# schematic.net
KiCad netlist of a schematic drawn in EAGLE
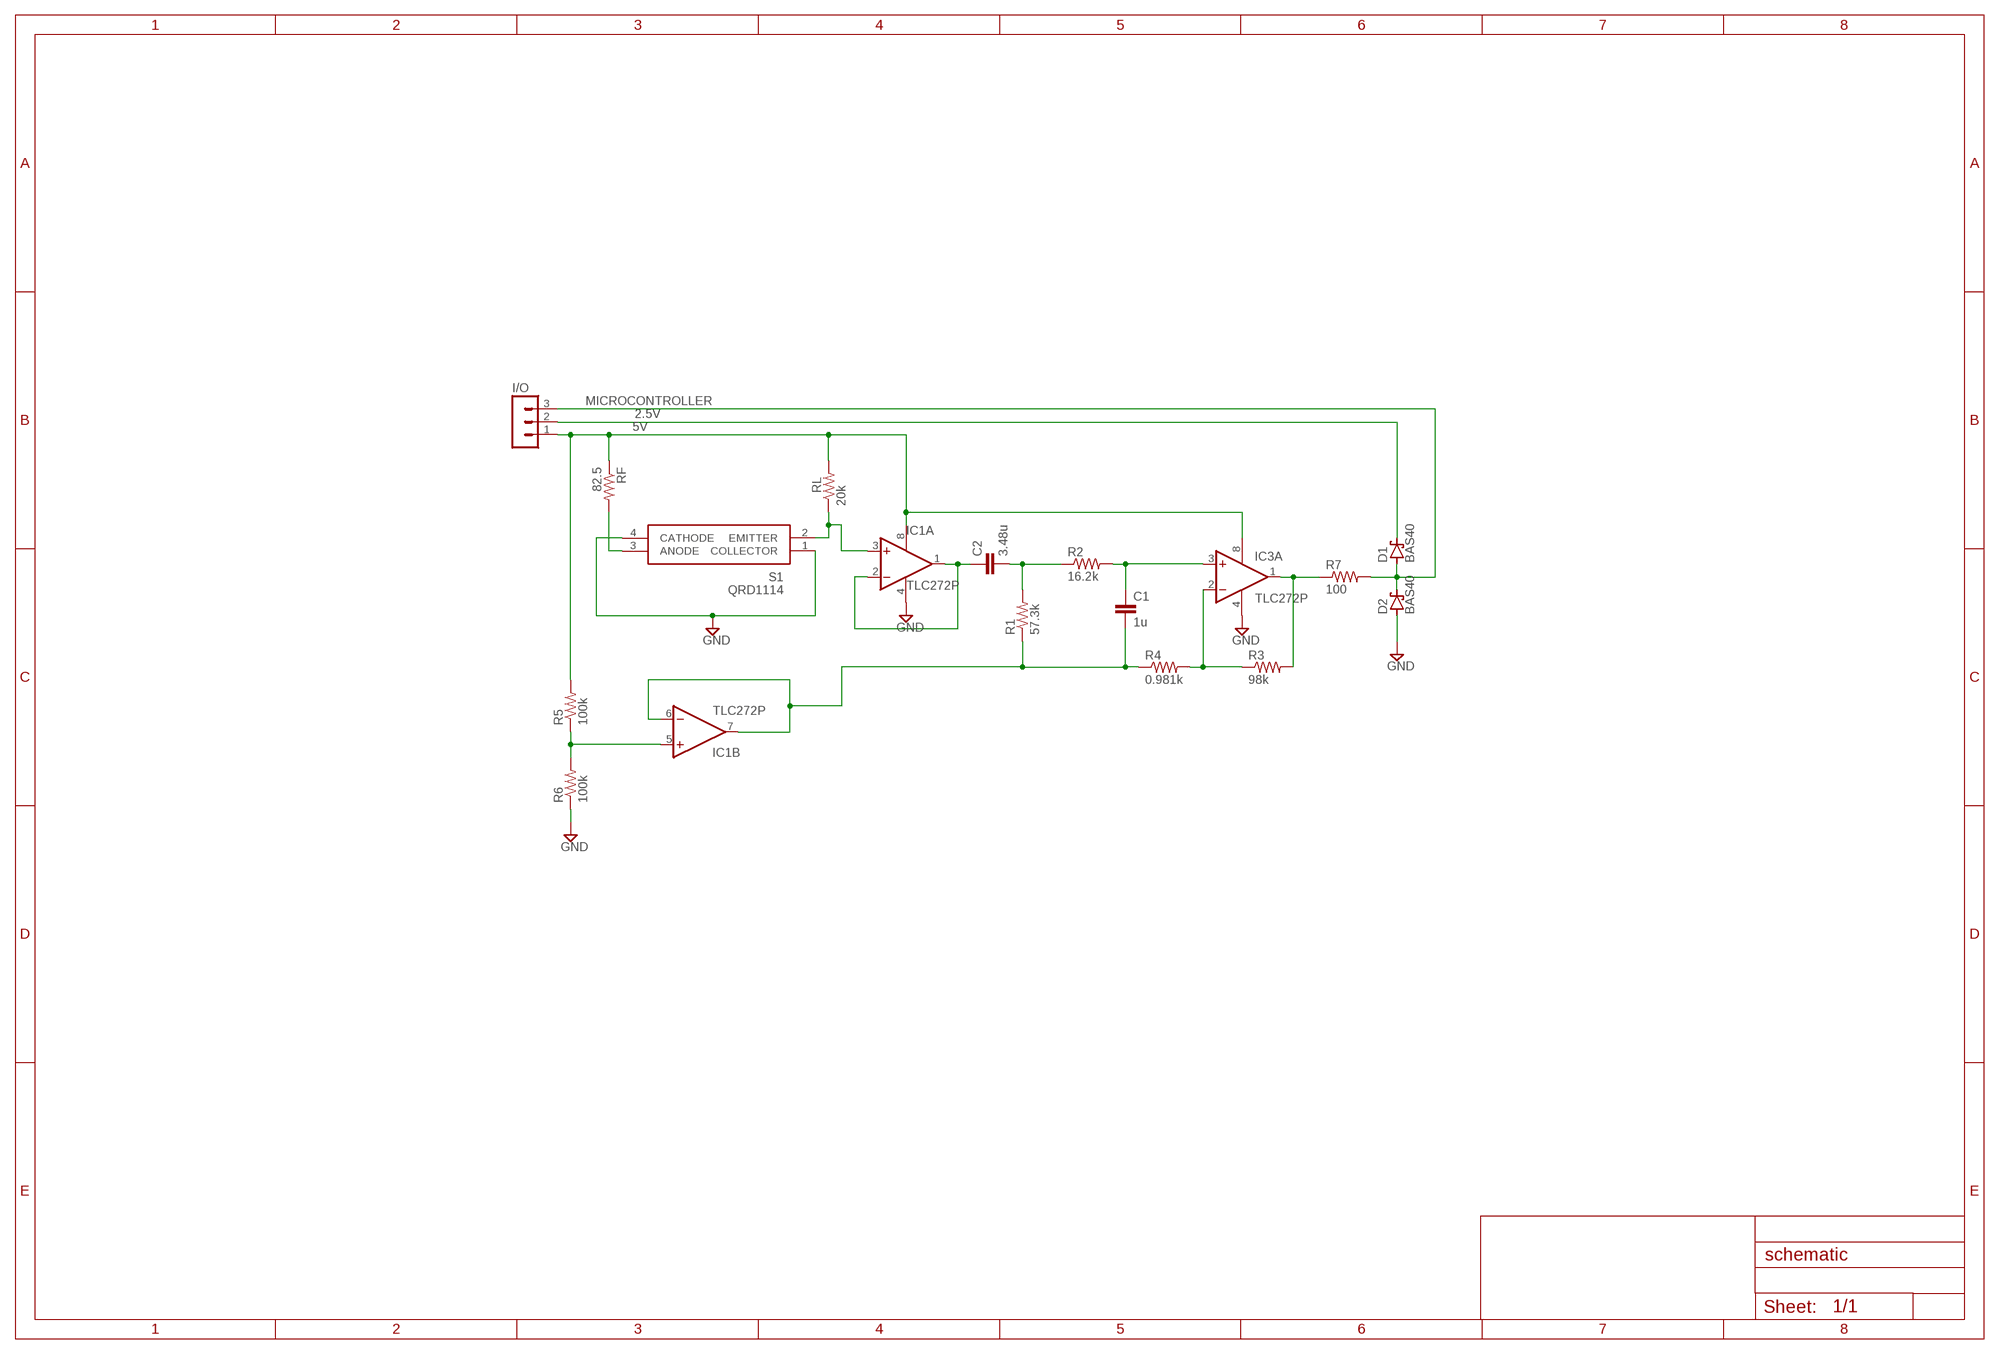
[diagram p0: schematic, sheet 1]

(export (version "E")
  (design (tool "Eeschema 10.0.6"))
  (components
    (comp (ref "C1")
      (value "1u")
      (footprint "eagle-import:C0402")
      (libsource (lib "eagle-import") (part "C-EUC0402"))
    )
    (comp (ref "C2")
      (value "3.48u")
      (footprint "eagle-import:C0402")
      (libsource (lib "eagle-import") (part "C-EUC0402"))
    )
    (comp (ref "D1")
      (value "BAS40")
      (footprint "eagle-import:SOT23")
      (libsource (lib "eagle-import") (part "BAS40"))
    )
    (comp (ref "D2")
      (value "BAS40")
      (footprint "eagle-import:SOT23")
      (libsource (lib "eagle-import") (part "BAS40"))
    )
    (comp (ref "I/O")
      (value "MA03-1")
      (footprint "eagle-import:MA03-1")
      (libsource (lib "eagle-import") (part "MA03-1"))
    )
    (comp (ref "IC1")
      (value "TLC272P")
      (footprint "eagle-import:DIL08")
      (libsource (lib "eagle-import") (part "TLC272P"))
    )
    (comp (ref "IC3")
      (value "TLC272P")
      (footprint "eagle-import:DIL08")
      (libsource (lib "eagle-import") (part "TLC272P"))
    )
    (comp (ref "R1")
      (value "57.3k")
      (footprint "eagle-import:M0805")
      (libsource (lib "eagle-import") (part "R-US_M0805"))
    )
    (comp (ref "R2")
      (value "16.2k")
      (footprint "eagle-import:M0805")
      (libsource (lib "eagle-import") (part "R-US_M0805"))
    )
    (comp (ref "R3")
      (value "98k")
      (footprint "eagle-import:M0805")
      (libsource (lib "eagle-import") (part "R-US_M0805"))
    )
    (comp (ref "R4")
      (value "0.981k")
      (footprint "eagle-import:M0805")
      (libsource (lib "eagle-import") (part "R-US_M0805"))
    )
    (comp (ref "R5")
      (value "100k")
      (footprint "eagle-import:M0805")
      (libsource (lib "eagle-import") (part "R-US_M0805"))
    )
    (comp (ref "R6")
      (value "100k")
      (footprint "eagle-import:0204_5")
      (libsource (lib "eagle-import") (part "R-US_0204/5"))
    )
    (comp (ref "R7")
      (value "100")
      (footprint "eagle-import:M0805")
      (libsource (lib "eagle-import") (part "R-US_M0805"))
    )
    (comp (ref "RF")
      (value "82.5")
      (footprint "eagle-import:M0805")
      (libsource (lib "eagle-import") (part "R-US_M0805"))
    )
    (comp (ref "RL")
      (value "20k")
      (footprint "eagle-import:M0805")
      (libsource (lib "eagle-import") (part "R-US_M0805"))
    )
    (comp (ref "S1")
      (value "QRD1114")
      (footprint "eagle-import:CUSTOM_4L")
      (fields (field (name "MOUSER_PART_NUMBER") "512-QRD1114"))
      (libsource (lib "eagle-import") (part "QRD1114"))
    )
  )
  (nets
    (net (code "1") (name "/2.5V") (class "Default")
      (node (ref "D1") (pin "3") (pinfunction "C_3") (pintype "passive"))
      (node (ref "I/O") (pin "2") (pinfunction "2_2") (pintype "passive"))
    )
    (net (code "2") (name "/5V") (class "Default")
      (node (ref "I/O") (pin "1") (pinfunction "1_1") (pintype "passive"))
      (node (ref "IC1") (pin "8") (pinfunction "V+_8") (pintype "power_in"))
      (node (ref "IC3") (pin "8") (pinfunction "V+_8") (pintype "power_in"))
      (node (ref "R5") (pin "2") (pinfunction "2_2") (pintype "passive"))
      (node (ref "RF") (pin "1") (pinfunction "1_1") (pintype "passive"))
      (node (ref "RL") (pin "2") (pinfunction "2_2") (pintype "passive"))
    )
    (net (code "3") (name "/MICROCONTROLLER") (class "Default")
      (node (ref "D1") (pin "1") (pinfunction "A_1") (pintype "passive"))
      (node (ref "D2") (pin "3") (pinfunction "C_3") (pintype "passive"))
      (node (ref "I/O") (pin "3") (pinfunction "3_3") (pintype "passive"))
      (node (ref "R7") (pin "2") (pinfunction "2_2") (pintype "passive"))
    )
    (net (code "4") (name "GND") (class "Default")
      (node (ref "D2") (pin "1") (pinfunction "A_1") (pintype "passive"))
      (node (ref "IC1") (pin "4") (pinfunction "V-_4") (pintype "power_in"))
      (node (ref "IC3") (pin "4") (pinfunction "V-_4") (pintype "power_in"))
      (node (ref "R6") (pin "1") (pinfunction "1_1") (pintype "passive"))
      (node (ref "S1") (pin "1") (pinfunction "COLLECTOR_1") (pintype "bidirectional"))
      (node (ref "S1") (pin "4") (pinfunction "CATHODE_4") (pintype "bidirectional"))
    )
    (net (code "5") (name "Net-(C2-Pad2)") (class "Default")
      (node (ref "C2") (pin "2") (pinfunction "2_2") (pintype "passive"))
      (node (ref "R1") (pin "2") (pinfunction "2_2") (pintype "passive"))
      (node (ref "R2") (pin "1") (pinfunction "1_1") (pintype "passive"))
    )
    (net (code "6") (name "Net-(IC1A-+IN)") (class "Default")
      (node (ref "IC1") (pin "3") (pinfunction "+IN_3") (pintype "input"))
      (node (ref "RL") (pin "1") (pinfunction "1_1") (pintype "passive"))
      (node (ref "S1") (pin "2") (pinfunction "EMITTER_2") (pintype "bidirectional"))
    )
    (net (code "7") (name "Net-(IC1A--IN)") (class "Default")
      (node (ref "C2") (pin "1") (pinfunction "1_1") (pintype "passive"))
      (node (ref "IC1") (pin "1") (pinfunction "OUT_1") (pintype "output"))
      (node (ref "IC1") (pin "2") (pinfunction "-IN_2") (pintype "input"))
    )
    (net (code "8") (name "Net-(IC1B-+IN)") (class "Default")
      (node (ref "IC1") (pin "5") (pinfunction "+IN_5") (pintype "input"))
      (node (ref "R5") (pin "1") (pinfunction "1_1") (pintype "passive"))
      (node (ref "R6") (pin "2") (pinfunction "2_2") (pintype "passive"))
    )
    (net (code "9") (name "Net-(IC1B--IN)") (class "Default")
      (node (ref "C1") (pin "2") (pinfunction "2_2") (pintype "passive"))
      (node (ref "IC1") (pin "6") (pinfunction "-IN_6") (pintype "input"))
      (node (ref "IC1") (pin "7") (pinfunction "OUT_7") (pintype "output"))
      (node (ref "R1") (pin "1") (pinfunction "1_1") (pintype "passive"))
      (node (ref "R4") (pin "1") (pinfunction "1_1") (pintype "passive"))
    )
    (net (code "10") (name "Net-(IC3A-+IN)") (class "Default")
      (node (ref "C1") (pin "1") (pinfunction "1_1") (pintype "passive"))
      (node (ref "IC3") (pin "3") (pinfunction "+IN_3") (pintype "input"))
      (node (ref "R2") (pin "2") (pinfunction "2_2") (pintype "passive"))
    )
    (net (code "11") (name "Net-(IC3A--IN)") (class "Default")
      (node (ref "IC3") (pin "2") (pinfunction "-IN_2") (pintype "input"))
      (node (ref "R3") (pin "1") (pinfunction "1_1") (pintype "passive"))
      (node (ref "R4") (pin "2") (pinfunction "2_2") (pintype "passive"))
    )
    (net (code "12") (name "Net-(IC3A-OUT)") (class "Default")
      (node (ref "IC3") (pin "1") (pinfunction "OUT_1") (pintype "output"))
      (node (ref "R3") (pin "2") (pinfunction "2_2") (pintype "passive"))
      (node (ref "R7") (pin "1") (pinfunction "1_1") (pintype "passive"))
    )
    (net (code "13") (name "Net-(S1-ANODE)") (class "Default")
      (node (ref "RF") (pin "2") (pinfunction "2_2") (pintype "passive"))
      (node (ref "S1") (pin "3") (pinfunction "ANODE_3") (pintype "bidirectional"))
    )
  )
)
